# Transfer_Circuit.net
KiCad netlist of a schematic drawn in Altium Designer
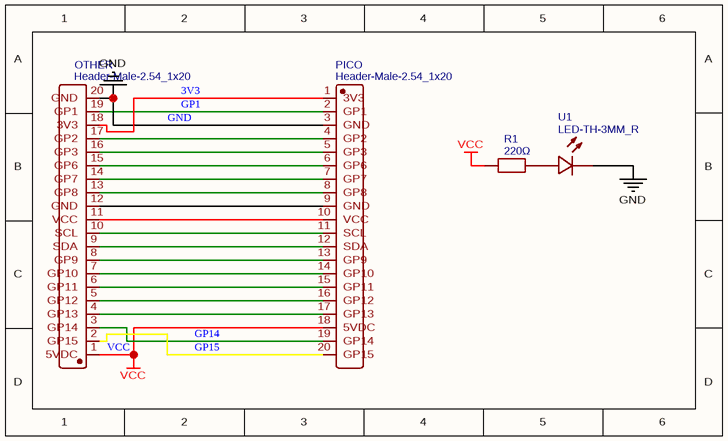
[diagram p0: Transfer Circuit.schdoc]

(export (version "E")
  (design (tool "Eeschema 10.0.6"))
  (components
    (comp (ref "OTHER")
      (value "Header-Male-2.54_1x20")
      (fields (field (name "MANUFACTURER") "BOOMELE(博穆精密)"))
      (libsource (lib "altium-import") (part "root_2_Header-Male-2.54_1x20_"))
    )
    (comp (ref "PICO")
      (value "Header-Male-2.54_1x20")
      (fields (field (name "MANUFACTURER") "BOOMELE(博穆精密)"))
      (libsource (lib "altium-import") (part "root_0_Header-Male-2.54_1x20_"))
    )
    (comp (ref "R1")
      (value "220Ω")
      (fields
        (field (name "MANUFACTURER") "Huaxing Mechanical-Elec.")
        (field (name "MANUFACTURER PART") "MF1/4W-20KΩ±1%T52")
        (field (name "CONTRIBUTOR") "LCSC")
      )
      (libsource (lib "altium-import") (part "root_0_220Ω_"))
    )
    (comp (ref "U1")
      (value "LED-TH-3MM_R")
      (fields (field (name "CONTRIBUTOR") "LCSC"))
      (libsource (lib "altium-import") (part "root_0_LED-TH-3MM_R_"))
    )
  )
  (nets
    (net (code "1") (name "/3V3") (class "Default")
      (node (ref "OTHER") (pin "18") (pinfunction "3V3_18") (pintype "passive"))
      (node (ref "PICO") (pin "1") (pinfunction "3V3_1") (pintype "passive"))
    )
    (net (code "2") (name "/GP1") (class "Default")
      (node (ref "OTHER") (pin "19") (pinfunction "GP1_19") (pintype "passive"))
      (node (ref "PICO") (pin "2") (pinfunction "GP1_2") (pintype "passive"))
    )
    (net (code "3") (name "/GP14") (class "Default")
      (node (ref "OTHER") (pin "3") (pinfunction "GP14_3") (pintype "passive"))
      (node (ref "PICO") (pin "19") (pinfunction "GP14_19") (pintype "passive"))
    )
    (net (code "4") (name "/GP15") (class "Default")
      (node (ref "OTHER") (pin "2") (pinfunction "GP15_2") (pintype "passive"))
      (node (ref "PICO") (pin "20") (pinfunction "GP15_20") (pintype "passive"))
    )
    (net (code "5") (name "GND") (class "Default")
      (node (ref "OTHER") (pin "20") (pinfunction "GND_20") (pintype "passive"))
      (node (ref "PICO") (pin "3") (pinfunction "GND_3") (pintype "passive"))
      (node (ref "U1") (pin "2") (pinfunction "2_2") (pintype "passive"))
    )
    (net (code "6") (name "Net-(OTHER-GND-Pad12)") (class "Default")
      (node (ref "OTHER") (pin "12") (pinfunction "GND_12") (pintype "passive"))
      (node (ref "PICO") (pin "9") (pinfunction "GND_9") (pintype "passive"))
    )
    (net (code "7") (name "Net-(OTHER-GP2)") (class "Default")
      (node (ref "OTHER") (pin "17") (pinfunction "GP2_17") (pintype "passive"))
      (node (ref "PICO") (pin "4") (pinfunction "GP2_4") (pintype "passive"))
    )
    (net (code "8") (name "Net-(OTHER-GP3)") (class "Default")
      (node (ref "OTHER") (pin "16") (pinfunction "GP3_16") (pintype "passive"))
      (node (ref "PICO") (pin "5") (pinfunction "GP3_5") (pintype "passive"))
    )
    (net (code "9") (name "Net-(OTHER-GP6)") (class "Default")
      (node (ref "OTHER") (pin "15") (pinfunction "GP6_15") (pintype "passive"))
      (node (ref "PICO") (pin "6") (pinfunction "GP6_6") (pintype "passive"))
    )
    (net (code "10") (name "Net-(OTHER-GP7)") (class "Default")
      (node (ref "OTHER") (pin "14") (pinfunction "GP7_14") (pintype "passive"))
      (node (ref "PICO") (pin "7") (pinfunction "GP7_7") (pintype "passive"))
    )
    (net (code "11") (name "Net-(OTHER-GP8)") (class "Default")
      (node (ref "OTHER") (pin "13") (pinfunction "GP8_13") (pintype "passive"))
      (node (ref "PICO") (pin "8") (pinfunction "GP8_8") (pintype "passive"))
    )
    (net (code "12") (name "Net-(OTHER-GP9)") (class "Default")
      (node (ref "OTHER") (pin "8") (pinfunction "GP9_8") (pintype "passive"))
      (node (ref "PICO") (pin "13") (pinfunction "GP9_13") (pintype "passive"))
    )
    (net (code "13") (name "Net-(OTHER-GP10)") (class "Default")
      (node (ref "OTHER") (pin "7") (pinfunction "GP10_7") (pintype "passive"))
      (node (ref "PICO") (pin "14") (pinfunction "GP10_14") (pintype "passive"))
    )
    (net (code "14") (name "Net-(OTHER-GP11)") (class "Default")
      (node (ref "OTHER") (pin "6") (pinfunction "GP11_6") (pintype "passive"))
      (node (ref "PICO") (pin "15") (pinfunction "GP11_15") (pintype "passive"))
    )
    (net (code "15") (name "Net-(OTHER-GP12)") (class "Default")
      (node (ref "OTHER") (pin "5") (pinfunction "GP12_5") (pintype "passive"))
      (node (ref "PICO") (pin "16") (pinfunction "GP12_16") (pintype "passive"))
    )
    (net (code "16") (name "Net-(OTHER-GP13)") (class "Default")
      (node (ref "OTHER") (pin "4") (pinfunction "GP13_4") (pintype "passive"))
      (node (ref "PICO") (pin "17") (pinfunction "GP13_17") (pintype "passive"))
    )
    (net (code "17") (name "Net-(OTHER-SCL)") (class "Default")
      (node (ref "OTHER") (pin "10") (pinfunction "SCL_10") (pintype "passive"))
      (node (ref "PICO") (pin "11") (pinfunction "SCL_11") (pintype "passive"))
    )
    (net (code "18") (name "Net-(OTHER-SDA)") (class "Default")
      (node (ref "OTHER") (pin "9") (pinfunction "SDA_9") (pintype "passive"))
      (node (ref "PICO") (pin "12") (pinfunction "SDA_12") (pintype "passive"))
    )
    (net (code "19") (name "Net-(OTHER-VCC)") (class "Default")
      (node (ref "OTHER") (pin "11") (pinfunction "VCC_11") (pintype "passive"))
      (node (ref "PICO") (pin "10") (pinfunction "VCC_10") (pintype "passive"))
    )
    (net (code "20") (name "Net-(R1-Pad2)") (class "Default")
      (node (ref "R1") (pin "2") (pinfunction "2_2") (pintype "passive"))
      (node (ref "U1") (pin "1") (pinfunction "1_1") (pintype "passive"))
    )
    (net (code "21") (name "VCC") (class "Default")
      (node (ref "OTHER") (pin "1") (pinfunction "5VDC_1") (pintype "passive"))
      (node (ref "PICO") (pin "18") (pinfunction "5VDC_18") (pintype "passive"))
      (node (ref "R1") (pin "1") (pinfunction "1_1") (pintype "passive"))
    )
  )
)
